# 03_Peripherals.net
KiCad netlist of a schematic drawn in Altium Designer
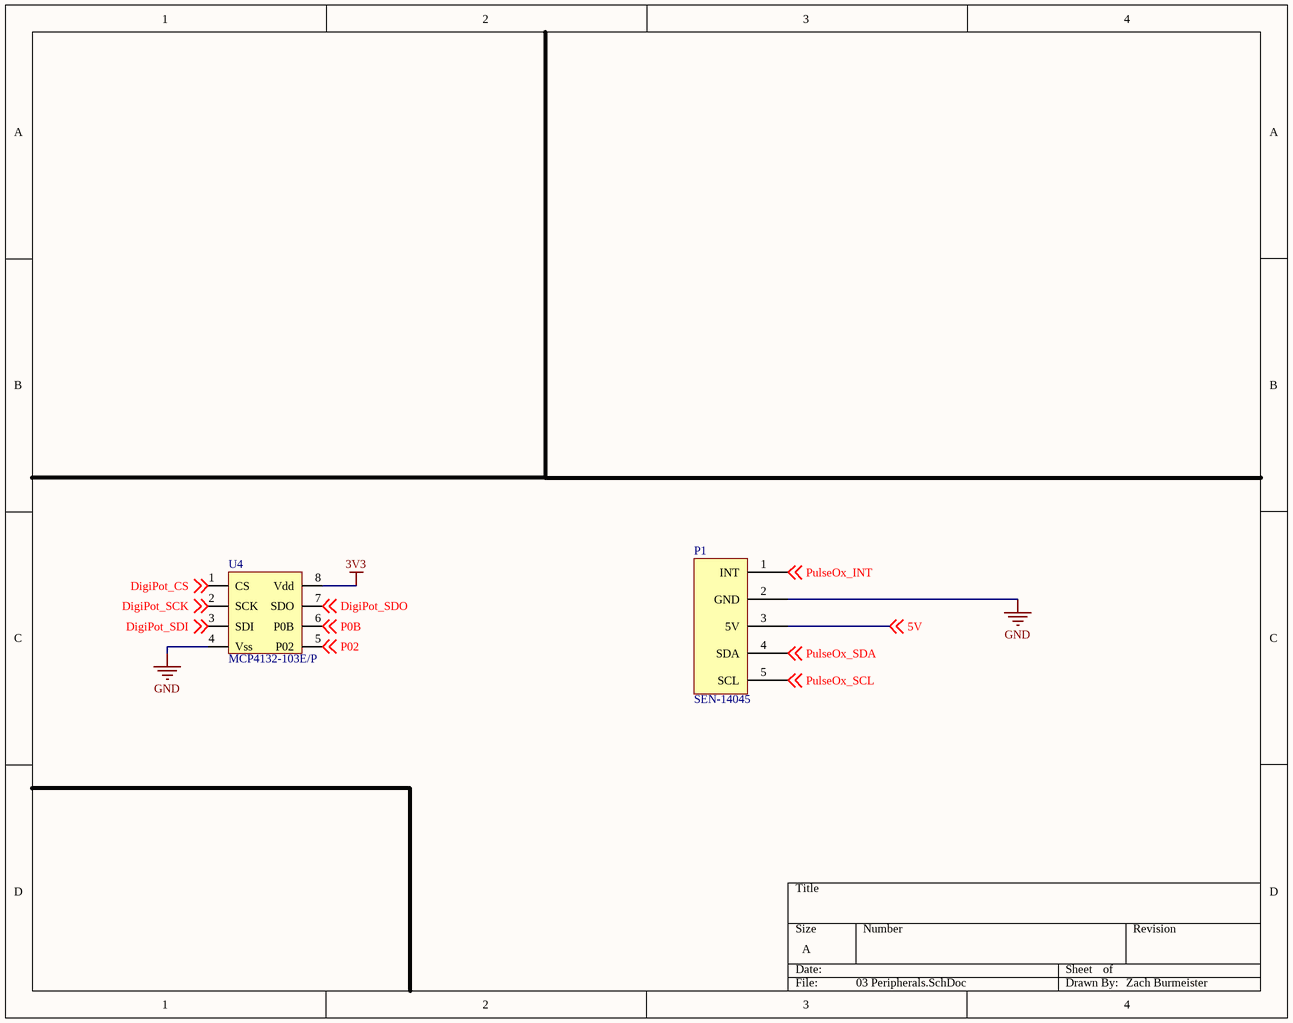
[diagram p0: 03 Peripherals.SchDoc]

(export (version "E")
  (design (tool "Eeschema 10.0.6"))
  (components
    (comp (ref "P1")
      (value "SEN-14045")
      (footprint "5 pin header")
      (description "Pulse Ox")
      (libsource (lib "Schlib1") (part "SEN-14045"))
    )
    (comp (ref "U4")
      (value "MCP4132-103E/P")
      (footprint "DIP8")
      (description "Digital Pot")
      (libsource (lib "Schlib1") (part "MCP4132-103E/P"))
    )
  )
  (nets
    (net (code "1") (name "3V3") (class "Default")
      (node (ref "U4") (pin "8") (pinfunction "Vdd_8") (pintype "passive"))
    )
    (net (code "2") (name "5V") (class "Default")
      (node (ref "P1") (pin "3") (pinfunction "5V_3") (pintype "passive"))
    )
    (net (code "3") (name "DigiPot_CS") (class "Default")
      (node (ref "U4") (pin "1") (pinfunction "CS_1") (pintype "passive"))
    )
    (net (code "4") (name "DigiPot_SCK") (class "Default")
      (node (ref "U4") (pin "2") (pinfunction "SCK_2") (pintype "passive"))
    )
    (net (code "5") (name "DigiPot_SDI") (class "Default")
      (node (ref "U4") (pin "3") (pinfunction "SDI_3") (pintype "passive"))
    )
    (net (code "6") (name "DigiPot_SDO") (class "Default")
      (node (ref "U4") (pin "7") (pinfunction "SDO_7") (pintype "passive"))
    )
    (net (code "7") (name "GND") (class "Default")
      (node (ref "P1") (pin "2") (pinfunction "GND_2") (pintype "passive"))
      (node (ref "U4") (pin "4") (pinfunction "Vss_4") (pintype "passive"))
    )
    (net (code "8") (name "P0B") (class "Default")
      (node (ref "U4") (pin "6") (pinfunction "P0B_6") (pintype "passive"))
    )
    (net (code "9") (name "P02") (class "Default")
      (node (ref "U4") (pin "5") (pinfunction "P02_5") (pintype "passive"))
    )
    (net (code "10") (name "PulseOx_INT") (class "Default")
      (node (ref "P1") (pin "1") (pinfunction "INT_1") (pintype "passive"))
    )
    (net (code "11") (name "PulseOx_SCL") (class "Default")
      (node (ref "P1") (pin "5") (pinfunction "SCL_5") (pintype "passive"))
    )
    (net (code "12") (name "PulseOx_SDA") (class "Default")
      (node (ref "P1") (pin "4") (pinfunction "SDA_4") (pintype "passive"))
    )
  )
)
